# wordclock_zero.net
KiCad netlist of a schematic drawn in EAGLE
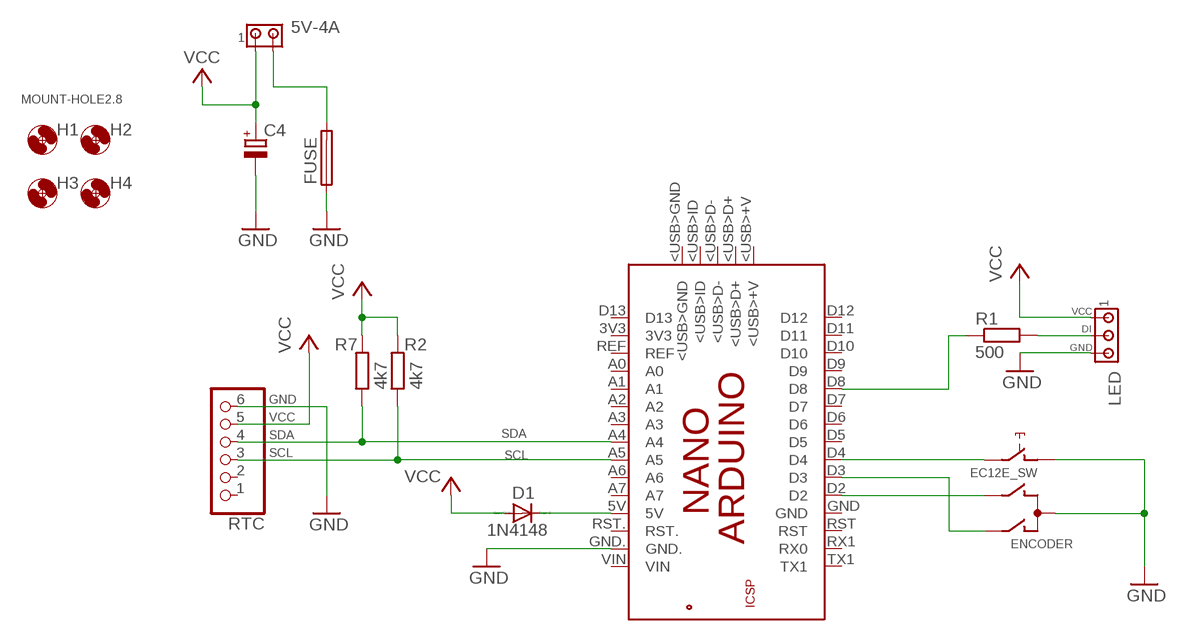
[diagram p0: schematic, sheet 1]

(export (version "E")
  (design (tool "Eeschema 10.0.6"))
  (components
    (comp (ref "5V-4A")
      (value "5V-4A")
      (footprint "eagle-import:1X2MTA")
      (libsource (lib "eagle-import") (part "MTA02-156"))
    )
    (comp (ref "C4")
      (value "CPOL-EUE5-10.5")
      (footprint "eagle-import:E5-10,5")
      (libsource (lib "eagle-import") (part "CPOL-EUE5-10.5"))
    )
    (comp (ref "D1")
      (value "1N4148")
      (footprint "eagle-import:DO35-10")
      (libsource (lib "eagle-import") (part "1N4148DO35-10"))
    )
    (comp (ref "ENCODER")
      (value "EC12E_SW")
      (footprint "eagle-import:ALPS_EC12E_SW")
      (fields (field (name "MPN") "EC12E2424407"))
      (libsource (lib "eagle-import") (part "EC12E_SW"))
    )
    (comp (ref "FUSE")
      (value "FUSELITTLEFUSE")
      (footprint "eagle-import:LITTLEFUSE")
      (libsource (lib "eagle-import") (part "FUSELITTLEFUSE"))
    )
    (comp (ref "H1")
      (value "MOUNT-HOLE2.8")
      (footprint "eagle-import:2,8")
      (libsource (lib "eagle-import") (part "MOUNT-HOLE2.8"))
    )
    (comp (ref "H2")
      (value "MOUNT-HOLE2.8")
      (footprint "eagle-import:2,8")
      (libsource (lib "eagle-import") (part "MOUNT-HOLE2.8"))
    )
    (comp (ref "H3")
      (value "MOUNT-HOLE2.8")
      (footprint "eagle-import:2,8")
      (libsource (lib "eagle-import") (part "MOUNT-HOLE2.8"))
    )
    (comp (ref "H4")
      (value "MOUNT-HOLE2.8")
      (footprint "eagle-import:2,8")
      (libsource (lib "eagle-import") (part "MOUNT-HOLE2.8"))
    )
    (comp (ref "LED")
      (value "MTA03-156")
      (footprint "eagle-import:1X3MTA")
      (libsource (lib "eagle-import") (part "MTA03-156"))
    )
    (comp (ref "PCB2")
      (value "ARDUINO_NANO")
      (footprint "eagle-import:ARDUINO_NANO")
      (libsource (lib "eagle-import") (part "ARDUINO_NANO"))
    )
    (comp (ref "R1")
      (value "500")
      (footprint "eagle-import:0207_7")
      (libsource (lib "eagle-import") (part "resistor_R-EU_0207/7"))
    )
    (comp (ref "R2")
      (value "4k7")
      (footprint "eagle-import:0207_10")
      (libsource (lib "eagle-import") (part "R-EU_0207/10"))
    )
    (comp (ref "R7")
      (value "4k7")
      (footprint "eagle-import:0207_10")
      (libsource (lib "eagle-import") (part "R-EU_0207/10"))
    )
    (comp (ref "RTC")
      (value "PINHD-1X6")
      (footprint "eagle-import:1X06")
      (libsource (lib "eagle-import") (part "PINHD-1X6"))
    )
  )
  (nets
    (net (code "1") (name "DI") (class "Default")
      (node (ref "LED") (pin "2") (pinfunction "2_2") (pintype "passive"))
      (node (ref "R1") (pin "2") (pinfunction "2_2") (pintype "passive"))
    )
    (net (code "2") (name "GND") (class "Default")
      (node (ref "C4") (pin "-") (pinfunction "-_-") (pintype "passive"))
      (node (ref "ENCODER") (pin "C") (pinfunction "C_C") (pintype "passive"))
      (node (ref "ENCODER") (pin "D") (pinfunction "1_D") (pintype "passive"))
      (node (ref "FUSE") (pin "1") (pinfunction "1_1") (pintype "passive"))
      (node (ref "LED") (pin "3") (pinfunction "3_3") (pintype "passive"))
      (node (ref "PCB2") (pin "GND.") (pinfunction "GND._GND.") (pintype "bidirectional"))
      (node (ref "RTC") (pin "6") (pinfunction "6_6") (pintype "passive"))
    )
    (net (code "3") (name "Net-(5V-4A-Pad2)") (class "Default")
      (node (ref "5V-4A") (pin "2") (pinfunction "2_2") (pintype "passive"))
      (node (ref "FUSE") (pin "2") (pinfunction "2_2") (pintype "passive"))
    )
    (net (code "4") (name "Net-(D1-PadC)") (class "Default")
      (node (ref "D1") (pin "C") (pinfunction "C_C") (pintype "passive"))
      (node (ref "PCB2") (pin "5V") (pinfunction "5V_5V") (pintype "bidirectional"))
    )
    (net (code "5") (name "Net-(ENCODER-PadA)") (class "Default")
      (node (ref "ENCODER") (pin "A") (pinfunction "A_A") (pintype "passive"))
      (node (ref "PCB2") (pin "D3") (pinfunction "D3_D3") (pintype "bidirectional"))
    )
    (net (code "6") (name "Net-(ENCODER-PadB)") (class "Default")
      (node (ref "ENCODER") (pin "B") (pinfunction "B_B") (pintype "passive"))
      (node (ref "PCB2") (pin "D2") (pinfunction "D2_D2") (pintype "bidirectional"))
    )
    (net (code "7") (name "Net-(ENCODERB-2)") (class "Default")
      (node (ref "ENCODER") (pin "E") (pinfunction "2_E") (pintype "passive"))
      (node (ref "PCB2") (pin "D4") (pinfunction "D4_D4") (pintype "bidirectional"))
    )
    (net (code "8") (name "Net-(PCB2-PadD8)") (class "Default")
      (node (ref "PCB2") (pin "D8") (pinfunction "D8_D8") (pintype "bidirectional"))
      (node (ref "R1") (pin "1") (pinfunction "1_1") (pintype "passive"))
    )
    (net (code "9") (name "SCL") (class "Default")
      (node (ref "PCB2") (pin "A5") (pinfunction "A5_A5") (pintype "bidirectional"))
      (node (ref "R2") (pin "1") (pinfunction "1_1") (pintype "passive"))
      (node (ref "RTC") (pin "3") (pinfunction "3_3") (pintype "passive"))
    )
    (net (code "10") (name "SDA") (class "Default")
      (node (ref "PCB2") (pin "A4") (pinfunction "A4_A4") (pintype "bidirectional"))
      (node (ref "R7") (pin "1") (pinfunction "1_1") (pintype "passive"))
      (node (ref "RTC") (pin "4") (pinfunction "4_4") (pintype "passive"))
    )
    (net (code "11") (name "VCC") (class "Default")
      (node (ref "5V-4A") (pin "1") (pinfunction "1_1") (pintype "passive"))
      (node (ref "C4") (pin "+") (pinfunction "+_+") (pintype "passive"))
      (node (ref "D1") (pin "A") (pinfunction "A_A") (pintype "passive"))
      (node (ref "LED") (pin "1") (pinfunction "1_1") (pintype "passive"))
      (node (ref "R2") (pin "2") (pinfunction "2_2") (pintype "passive"))
      (node (ref "R7") (pin "2") (pinfunction "2_2") (pintype "passive"))
      (node (ref "RTC") (pin "5") (pinfunction "5_5") (pintype "passive"))
    )
    (net (code "12") (name "unconnected-(PCB2-Pad3V3)") (class "Default")
      (node (ref "PCB2") (pin "3V3") (pinfunction "3V3_3V3") (pintype "bidirectional"))
    )
    (net (code "13") (name "unconnected-(PCB2-Pad5V.)") (class "Default")
      (node (ref "PCB2") (pin "5V.") (pinfunction "5V._5V.") (pintype "bidirectional"))
    )
    (net (code "14") (name "unconnected-(PCB2-Pad<USB>+V)") (class "Default")
      (node (ref "PCB2") (pin "<USB>+V") (pinfunction "<USB>+V_<USB>+V") (pintype "bidirectional"))
    )
    (net (code "15") (name "unconnected-(PCB2-Pad<USB>D+)") (class "Default")
      (node (ref "PCB2") (pin "<USB>D+") (pinfunction "<USB>D+_<USB>D+") (pintype "bidirectional"))
    )
    (net (code "16") (name "unconnected-(PCB2-Pad<USB>D-)") (class "Default")
      (node (ref "PCB2") (pin "<USB>D-") (pinfunction "<USB>D-_<USB>D-") (pintype "bidirectional"))
    )
    (net (code "17") (name "unconnected-(PCB2-Pad<USB>GND)") (class "Default")
      (node (ref "PCB2") (pin "<USB>GND") (pinfunction "<USB>GND_<USB>GND") (pintype "bidirectional"))
    )
    (net (code "18") (name "unconnected-(PCB2-Pad<USB>ID)") (class "Default")
      (node (ref "PCB2") (pin "<USB>ID") (pinfunction "<USB>ID_<USB>ID") (pintype "bidirectional"))
    )
    (net (code "19") (name "unconnected-(PCB2-PadA0)") (class "Default")
      (node (ref "PCB2") (pin "A0") (pinfunction "A0_A0") (pintype "bidirectional"))
    )
    (net (code "20") (name "unconnected-(PCB2-PadA1)") (class "Default")
      (node (ref "PCB2") (pin "A1") (pinfunction "A1_A1") (pintype "bidirectional"))
    )
    (net (code "21") (name "unconnected-(PCB2-PadA2)") (class "Default")
      (node (ref "PCB2") (pin "A2") (pinfunction "A2_A2") (pintype "bidirectional"))
    )
    (net (code "22") (name "unconnected-(PCB2-PadA3)") (class "Default")
      (node (ref "PCB2") (pin "A3") (pinfunction "A3_A3") (pintype "bidirectional"))
    )
    (net (code "23") (name "unconnected-(PCB2-PadA6)") (class "Default")
      (node (ref "PCB2") (pin "A6") (pinfunction "A6_A6") (pintype "bidirectional"))
    )
    (net (code "24") (name "unconnected-(PCB2-PadA7)") (class "Default")
      (node (ref "PCB2") (pin "A7") (pinfunction "A7_A7") (pintype "bidirectional"))
    )
    (net (code "25") (name "unconnected-(PCB2-PadD5)") (class "Default")
      (node (ref "PCB2") (pin "D5") (pinfunction "D5_D5") (pintype "bidirectional"))
    )
    (net (code "26") (name "unconnected-(PCB2-PadD6)") (class "Default")
      (node (ref "PCB2") (pin "D6") (pinfunction "D6_D6") (pintype "bidirectional"))
    )
    (net (code "27") (name "unconnected-(PCB2-PadD7)") (class "Default")
      (node (ref "PCB2") (pin "D7") (pinfunction "D7_D7") (pintype "bidirectional"))
    )
    (net (code "28") (name "unconnected-(PCB2-PadD9)") (class "Default")
      (node (ref "PCB2") (pin "D9") (pinfunction "D9_D9") (pintype "bidirectional"))
    )
    (net (code "29") (name "unconnected-(PCB2-PadD10)") (class "Default")
      (node (ref "PCB2") (pin "D10") (pinfunction "D10_D10") (pintype "bidirectional"))
    )
    (net (code "30") (name "unconnected-(PCB2-PadD11)") (class "Default")
      (node (ref "PCB2") (pin "D11") (pinfunction "D11_D11") (pintype "bidirectional"))
    )
    (net (code "31") (name "unconnected-(PCB2-PadD12)") (class "Default")
      (node (ref "PCB2") (pin "D12") (pinfunction "D12_D12") (pintype "bidirectional"))
    )
    (net (code "32") (name "unconnected-(PCB2-PadD13)") (class "Default")
      (node (ref "PCB2") (pin "D13") (pinfunction "D13_D13") (pintype "bidirectional"))
    )
    (net (code "33") (name "unconnected-(PCB2-PadGND)") (class "Default")
      (node (ref "PCB2") (pin "GND") (pinfunction "GND_GND") (pintype "bidirectional"))
    )
    (net (code "34") (name "unconnected-(PCB2-PadGND_)") (class "Default")
      (node (ref "PCB2") (pin "GND_") (pinfunction "GND__GND_") (pintype "bidirectional"))
    )
    (net (code "35") (name "unconnected-(PCB2-PadMISO)") (class "Default")
      (node (ref "PCB2") (pin "MISO") (pinfunction "MISO_MISO") (pintype "bidirectional"))
    )
    (net (code "36") (name "unconnected-(PCB2-PadMOSI)") (class "Default")
      (node (ref "PCB2") (pin "MOSI") (pinfunction "MOSI_MOSI") (pintype "bidirectional"))
    )
    (net (code "37") (name "unconnected-(PCB2-PadREF)") (class "Default")
      (node (ref "PCB2") (pin "REF") (pinfunction "REF_REF") (pintype "bidirectional"))
    )
    (net (code "38") (name "unconnected-(PCB2-PadRESET..)") (class "Default")
      (node (ref "PCB2") (pin "RESET..") (pinfunction "RESET.._RESET..") (pintype "bidirectional"))
    )
    (net (code "39") (name "unconnected-(PCB2-PadRST)") (class "Default")
      (node (ref "PCB2") (pin "RST") (pinfunction "RST_RST") (pintype "bidirectional"))
    )
    (net (code "40") (name "unconnected-(PCB2-PadRST.)") (class "Default")
      (node (ref "PCB2") (pin "RST.") (pinfunction "RST._RST.") (pintype "bidirectional"))
    )
    (net (code "41") (name "unconnected-(PCB2-PadSCK)") (class "Default")
      (node (ref "PCB2") (pin "SCK") (pinfunction "SCK_SCK") (pintype "bidirectional"))
    )
    (net (code "42") (name "unconnected-(PCB2-PadTX1)") (class "Default")
      (node (ref "PCB2") (pin "TX1") (pinfunction "TX1_TX1") (pintype "bidirectional"))
    )
    (net (code "43") (name "unconnected-(PCB2-PadVIN)") (class "Default")
      (node (ref "PCB2") (pin "VIN") (pinfunction "VIN_VIN") (pintype "bidirectional"))
    )
    (net (code "44") (name "unconnected-(PCB2-RX0-PadRX1)") (class "Default")
      (node (ref "PCB2") (pin "RX1") (pinfunction "RX0_RX1") (pintype "bidirectional"))
    )
    (net (code "45") (name "unconnected-(RTC-Pad1)") (class "Default")
      (node (ref "RTC") (pin "1") (pinfunction "1_1") (pintype "passive"))
    )
    (net (code "46") (name "unconnected-(RTC-Pad2)") (class "Default")
      (node (ref "RTC") (pin "2") (pinfunction "2_2") (pintype "passive"))
    )
  )
)
